# Motor_Driver.net
KiCad netlist of a schematic drawn in Altium Designer
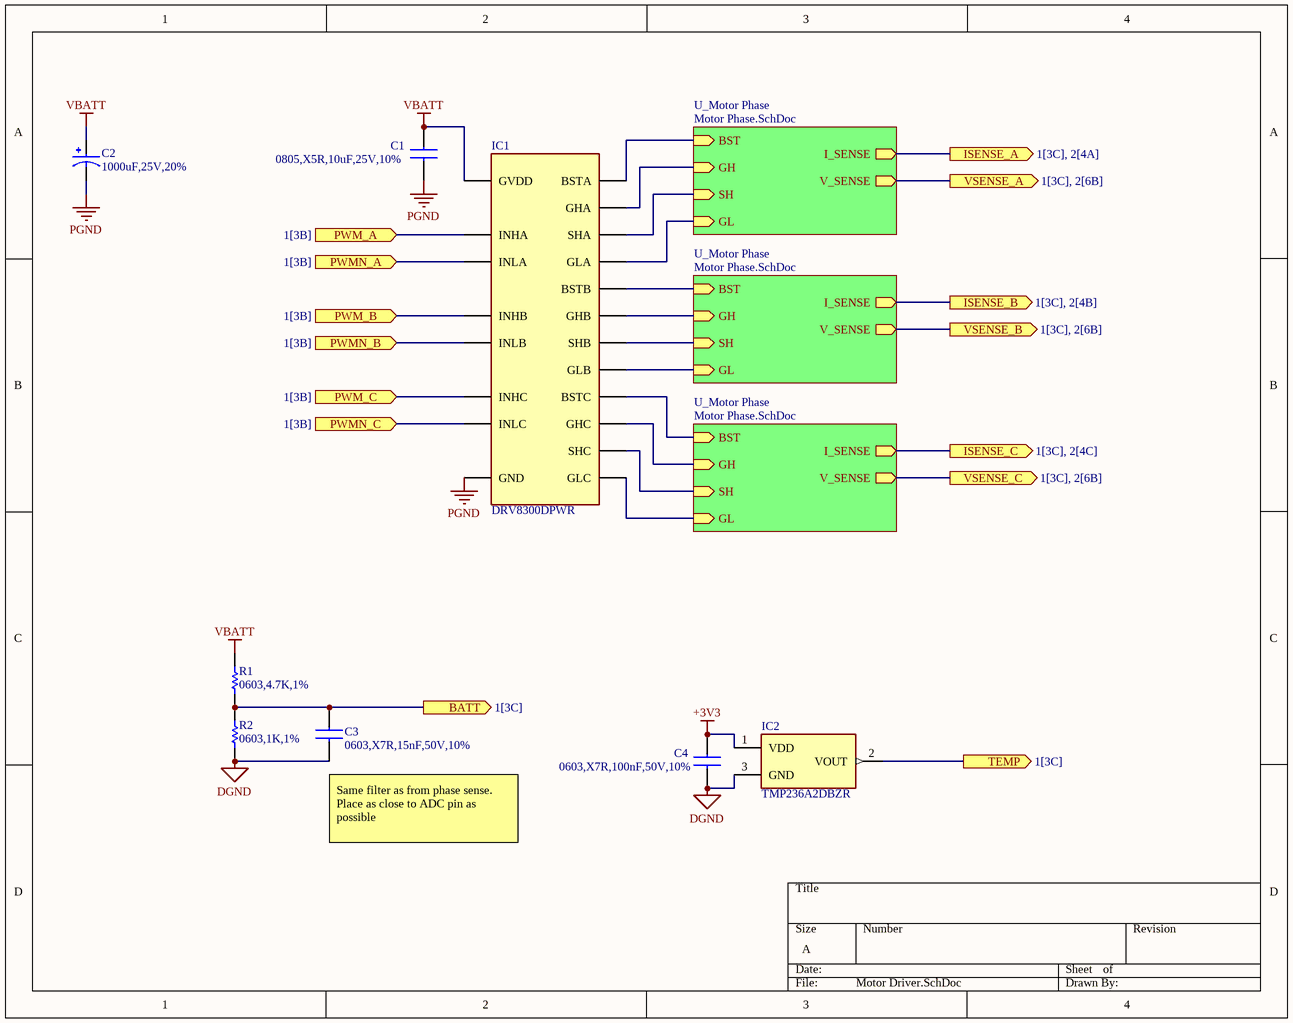
[diagram p0: Motor Driver.SchDoc]

(export (version "E")
  (design (tool "Eeschema 10.0.6"))
  (components
    (comp (ref "C1")
      (value "0805,X5R,10uF,25V,10%")
      (footprint "CAPC2012X145N")
      (description "10 µF ±10% 25V Ceramic Capacitor X5R 0805 (2012 Metric)")
      (fields
        (field (name "MANUFACTURER_PART_NUMBER") "CC0805KKX5R8BB106")
        (field (name "MOUSER PART NUMBER") "603-CC805KKX5R8BB106")
      )
      (libsource (lib "ESC") (part "CC0805KKX5R8BB106"))
    )
    (comp (ref "C2")
      (value "1000uF,25V,20%")
      (footprint "CAP-TH_BD10.0-P5.00-D1.0-FD")
      (description "1000uF 25V ±20% 870mA@120Hz Through Hole,D10xL16mm Aluminum Electrolytic Capacitors - Leaded ROHS")
      (fields (field (name "LCSC PART #") "C109451"))
      (libsource (lib "ESC") (part "25PK1000MEFC10*16"))
    )
    (comp (ref "C3")
      (value "0603,X7R,15nF,50V,10%")
      (footprint "CAPC1608X90N")
      (description "50V 15nF X7R ±10% 0603 Multilayer Ceramic Capacitors MLCC - SMD/SMT ROHS")
      (fields
        (field (name "MANUFACTURER_PART_NUMBER") "CC0603KRX7R9BB153")
        (field (name "MOUSER PART NUMBER") "603-CC603KRX7R9BB104")
      )
      (libsource (lib "ESC") (part "CC0603KRX7R9BB153"))
    )
    (comp (ref "C4")
      (value "0603,X7R,100nF,50V,10%")
      (footprint "CAPC1608X90N")
      (description "50V 100nF X7R ±10% 0603 Multilayer Ceramic Capacitors MLCC - SMD/SMT ROHS")
      (fields
        (field (name "MANUFACTURER_PART_NUMBER") "CC0603KRX7R9BB104")
        (field (name "MOUSER PART NUMBER") "603-CC603KRX7R9BB104")
      )
      (libsource (lib "ESC") (part "CC0603KRX7R9BB104"))
    )
    (comp (ref "IC1")
      (value "DRV8300DPWR")
      (footprint "ESC:SOP65P640X120-20N")
      (description "TSSOP-20 Brushless DC (BLDC) Motor Driver ROHS")
      (fields (field (name "MOUSER PART NUMBER") "595-DRV8300DPWR") (field (name "LCSC PART #") "C3036056"))
      (libsource (lib "ESC") (part "DRV8300DPWR"))
    )
    (comp (ref "IC2")
      (value "TMP236A2DBZR")
      (footprint "SOT95P237X112-3N")
      (description "Low-power and high-precision analog output temperature sensor")
      (fields (field (name "MOUSER PART NUMBER") "595-TMP236A2DBZR") (field (name "LCSC PART #") "C2859666"))
      (libsource (lib "ESC") (part "TMP236A2DBZR"))
    )
    (comp (ref "R1")
      (value "0603,4.7K,1%")
      (footprint "RESC1608X55N")
      (description "100mW Thick Film Resistor 75V ±100ppm/℃ ±1% 4.7kΩ 0603 Chip Resistor - Surface Mount ROHS")
      (fields
        (field (name "MANUFACTURER_PART_NUMBER") "RC0603FR-074K7L")
        (field (name "LCSC PART #") "C99782")
      )
      (libsource (lib "ESC") (part "RC0603FR-074K7L"))
    )
    (comp (ref "R2")
      (value "0603,1K,1%")
      (footprint "RESC1608X55N")
      (description "100mW Thick Film Resistor 75V ±100ppm/℃ ±1% 1kΩ 0603 Chip Resistor - Surface Mount ROHS")
      (fields
        (field (name "MANUFACTURER_PART_NUMBER") "RC0603FR-071KL")
        (field (name "LCSC PART #") "C22548")
      )
      (libsource (lib "ESC") (part "RC0603FR-071KL"))
    )
  )
  (nets
    (net (code "1") (name "+3V3") (class "Default")
      (node (ref "C4") (pin "2") (pinfunction "2_2") (pintype "passive"))
      (node (ref "IC2") (pin "1") (pinfunction "VDD_1") (pintype "power_in"))
    )
    (net (code "2") (name "/BATT") (class "Default")
      (node (ref "C3") (pin "2") (pinfunction "2_2") (pintype "passive"))
      (node (ref "R1") (pin "1") (pinfunction "1_1") (pintype "passive"))
      (node (ref "R2") (pin "2") (pinfunction "2_2") (pintype "passive"))
    )
    (net (code "3") (name "/BST") (class "Default")
      (node (ref "IC1") (pin "17") (pinfunction "BSTB_17") (pintype "passive"))
    )
    (net (code "4") (name "/BST_1") (class "Default")
      (node (ref "IC1") (pin "14") (pinfunction "BSTC_14") (pintype "passive"))
    )
    (net (code "5") (name "/BST_2") (class "Default")
      (node (ref "IC1") (pin "20") (pinfunction "BSTA_20") (pintype "passive"))
    )
    (net (code "6") (name "/GH") (class "Default")
      (node (ref "IC1") (pin "16") (pinfunction "GHB_16") (pintype "passive"))
    )
    (net (code "7") (name "/GH_1") (class "Default")
      (node (ref "IC1") (pin "13") (pinfunction "GHC_13") (pintype "passive"))
    )
    (net (code "8") (name "/GH_2") (class "Default")
      (node (ref "IC1") (pin "19") (pinfunction "GHA_19") (pintype "passive"))
    )
    (net (code "9") (name "/GL") (class "Default")
      (node (ref "IC1") (pin "10") (pinfunction "GLB_10") (pintype "passive"))
    )
    (net (code "10") (name "/GL_1") (class "Default")
      (node (ref "IC1") (pin "9") (pinfunction "GLC_9") (pintype "passive"))
    )
    (net (code "11") (name "/GL_2") (class "Default")
      (node (ref "IC1") (pin "11") (pinfunction "GLA_11") (pintype "passive"))
    )
    (net (code "15") (name "/PWMN_A") (class "Default")
      (node (ref "IC1") (pin "4") (pinfunction "INLA_4") (pintype "passive"))
    )
    (net (code "16") (name "/PWMN_B") (class "Default")
      (node (ref "IC1") (pin "5") (pinfunction "INLB_5") (pintype "passive"))
    )
    (net (code "17") (name "/PWMN_C") (class "Default")
      (node (ref "IC1") (pin "6") (pinfunction "INLC_6") (pintype "passive"))
    )
    (net (code "18") (name "/PWM_A") (class "Default")
      (node (ref "IC1") (pin "1") (pinfunction "INHA_1") (pintype "passive"))
    )
    (net (code "19") (name "/PWM_B") (class "Default")
      (node (ref "IC1") (pin "2") (pinfunction "INHB_2") (pintype "passive"))
    )
    (net (code "20") (name "/PWM_C") (class "Default")
      (node (ref "IC1") (pin "3") (pinfunction "INHC_3") (pintype "passive"))
    )
    (net (code "21") (name "/SH") (class "Default")
      (node (ref "IC1") (pin "15") (pinfunction "SHB_15") (pintype "passive"))
    )
    (net (code "22") (name "/SH_1") (class "Default")
      (node (ref "IC1") (pin "12") (pinfunction "SHC_12") (pintype "passive"))
    )
    (net (code "23") (name "/SH_2") (class "Default")
      (node (ref "IC1") (pin "18") (pinfunction "SHA_18") (pintype "passive"))
    )
    (net (code "24") (name "/TEMP") (class "Default")
      (node (ref "IC2") (pin "2") (pinfunction "VOUT_2") (pintype "output"))
    )
    (net (code "28") (name "DGND") (class "Default")
      (node (ref "C3") (pin "1") (pinfunction "1_1") (pintype "passive"))
      (node (ref "C4") (pin "1") (pinfunction "1_1") (pintype "passive"))
      (node (ref "IC2") (pin "3") (pinfunction "GND_3") (pintype "power_in"))
      (node (ref "R2") (pin "1") (pinfunction "1_1") (pintype "passive"))
    )
    (net (code "29") (name "PGND") (class "Default")
      (node (ref "C1") (pin "2") (pinfunction "2_2") (pintype "passive"))
      (node (ref "C2") (pin "2") (pinfunction "2_2") (pintype "passive"))
      (node (ref "IC1") (pin "8") (pinfunction "GND_8") (pintype "passive"))
    )
    (net (code "30") (name "VBATT") (class "Default")
      (node (ref "C1") (pin "1") (pinfunction "1_1") (pintype "passive"))
      (node (ref "C2") (pin "1") (pinfunction "1_1") (pintype "passive"))
      (node (ref "IC1") (pin "7") (pinfunction "GVDD_7") (pintype "passive"))
      (node (ref "R1") (pin "2") (pinfunction "2_2") (pintype "passive"))
    )
  )
)
